# Buzzer_SCH.net
KiCad netlist of a schematic drawn in Altium Designer
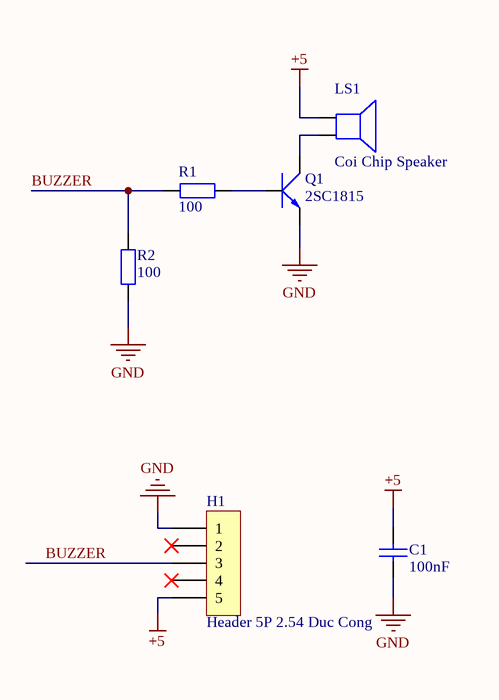
[diagram p0: Buzzer_SCH.SchDoc]

(export (version "E")
  (design (tool "Eeschema 10.0.6"))
  (components
    (comp (ref "C1")
      (value "100nF")
      (footprint "tu 0603")
      (description "Dán")
      (libsource (lib "namnt_Lib") (part "Tu 0603 104 50V 10%"))
    )
    (comp (ref "H1")
      (value "Header 5P 2.54 Duc Cong")
      (footprint "Header 5P DC 2.54")
      (description "Cắm")
      (libsource (lib "namnt_Lib") (part "Header 5P 2.54 Duc Cong"))
    )
    (comp (ref "LS1")
      (value "Coi Chip Speaker")
      (footprint "Coi Chip Speacker")
      (description "Còi chip")
      (libsource (lib "namnt_Lib") (part "Coi Chip Speaker"))
    )
    (comp (ref "Q1")
      (value "2SC1815")
      (footprint "SOT-23")
      (description "SOT-23")
      (libsource (lib "namnt_Lib") (part "Trans C1815 HF SMD"))
    )
    (comp (ref "R1")
      (value "100")
      (footprint "tro smd 0603")
      (description "Dán")
      (libsource (lib "namnt_Lib") (part "Tro 0603 5% 100R"))
    )
    (comp (ref "R2")
      (value "100")
      (footprint "tro smd 0603")
      (description "Dán")
      (libsource (lib "namnt_Lib") (part "Tro 0603 5% 100R"))
    )
  )
  (nets
    (net (code "1") (name "+5") (class "Default")
      (node (ref "C1") (pin "1") (pinfunction "1_1") (pintype "passive"))
      (node (ref "H1") (pin "5") (pinfunction "5_5") (pintype "passive"))
      (node (ref "LS1") (pin "1") (pinfunction "1_1") (pintype "passive"))
    )
    (net (code "2") (name "/BUZZER") (class "Default")
      (node (ref "H1") (pin "3") (pinfunction "3_3") (pintype "passive"))
      (node (ref "R1") (pin "1") (pinfunction "1_1") (pintype "passive"))
      (node (ref "R2") (pin "2") (pinfunction "2_2") (pintype "passive"))
    )
    (net (code "3") (name "GND") (class "Default")
      (node (ref "C1") (pin "2") (pinfunction "2_2") (pintype "passive"))
      (node (ref "H1") (pin "1") (pinfunction "1_1") (pintype "passive"))
      (node (ref "Q1") (pin "2") (pinfunction "E_2") (pintype "passive"))
      (node (ref "R2") (pin "1") (pinfunction "1_1") (pintype "passive"))
    )
    (net (code "4") (name "Net-(Q1-B)") (class "Default")
      (node (ref "Q1") (pin "1") (pinfunction "B_1") (pintype "passive"))
      (node (ref "R1") (pin "2") (pinfunction "2_2") (pintype "passive"))
    )
    (net (code "5") (name "Net-(Q1-C)") (class "Default")
      (node (ref "LS1") (pin "2") (pinfunction "2_2") (pintype "passive"))
      (node (ref "Q1") (pin "3") (pinfunction "C_3") (pintype "passive"))
    )
    (net (code "6") (name "unconnected-(H1-Pad2)") (class "Default")
      (node (ref "H1") (pin "2") (pinfunction "2_2") (pintype "passive+no_connect"))
    )
    (net (code "7") (name "unconnected-(H1-Pad4)") (class "Default")
      (node (ref "H1") (pin "4") (pinfunction "4_4") (pintype "passive+no_connect"))
    )
  )
)
